# WaterMonitorV2_1.net
KiCad netlist of a schematic drawn in EAGLE
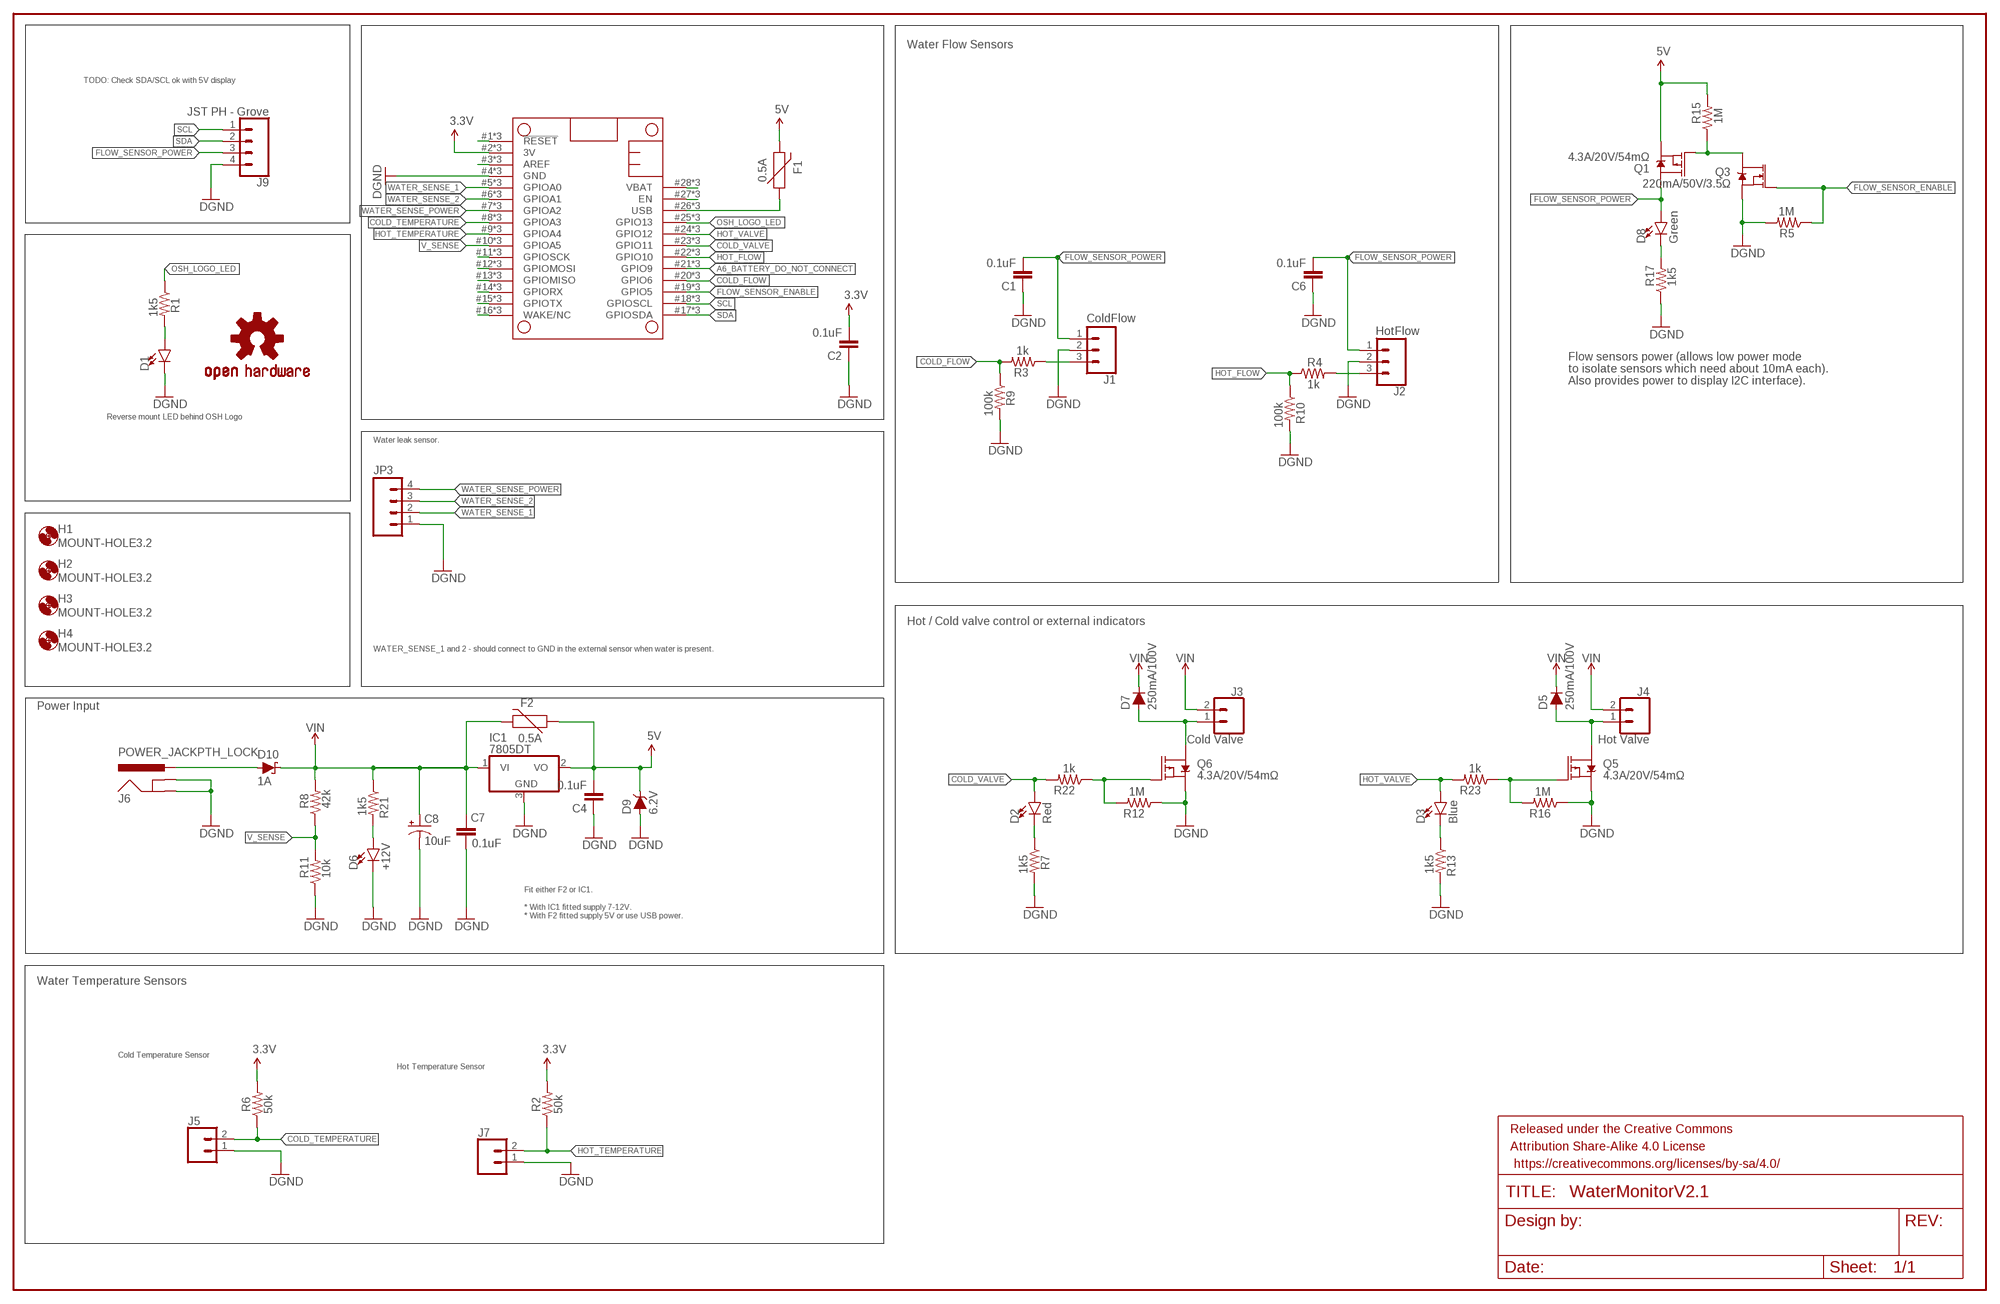
[diagram p0: schematic, sheet 1]

(export (version "E")
  (design (tool "Eeschema 10.0.6"))
  (components
    (comp (ref "C1")
      (value "0.1uF")
      (footprint "eagle-import:0805")
      (libsource (lib "eagle-import") (part "CAP0805"))
    )
    (comp (ref "C2")
      (value "0.1uF")
      (footprint "eagle-import:0805")
      (libsource (lib "eagle-import") (part "CAP0805"))
    )
    (comp (ref "C4")
      (value "0.1uF")
      (footprint "eagle-import:0805")
      (libsource (lib "eagle-import") (part "CAP0805"))
    )
    (comp (ref "C6")
      (value "0.1uF")
      (footprint "eagle-import:0805")
      (libsource (lib "eagle-import") (part "CAP0805"))
    )
    (comp (ref "C7")
      (value "0.1uF")
      (footprint "eagle-import:0805")
      (libsource (lib "eagle-import") (part "CAP0805"))
    )
    (comp (ref "C8")
      (value "10uF")
      (footprint "eagle-import:EIA3216")
      (libsource (lib "eagle-import") (part "10UF-POLAR-EIA3216-16V-10%(TANT)"))
    )
    (comp (ref "D1")
      (value "LED1206-BOTTOM")
      (footprint "eagle-import:LED-1206-BOTTOM")
      (libsource (lib "eagle-import") (part "LED1206-BOTTOM"))
    )
    (comp (ref "D2")
      (value "Red")
      (footprint "eagle-import:LED-1206")
      (libsource (lib "eagle-import") (part "LED-BLUE1206"))
    )
    (comp (ref "D3")
      (value "Blue")
      (footprint "eagle-import:LED-1206")
      (libsource (lib "eagle-import") (part "LED-BLUE1206"))
    )
    (comp (ref "D5")
      (value "250mA/100V")
      (footprint "eagle-import:SOD-323")
      (libsource (lib "eagle-import") (part "DIODE-BAS16J"))
    )
    (comp (ref "D6")
      (value "+12V")
      (footprint "eagle-import:LED-1206")
      (libsource (lib "eagle-import") (part "LED-BLUE1206"))
    )
    (comp (ref "D7")
      (value "250mA/100V")
      (footprint "eagle-import:SOD-323")
      (libsource (lib "eagle-import") (part "DIODE-BAS16J"))
    )
    (comp (ref "D8")
      (value "Green")
      (footprint "eagle-import:LED-1206")
      (libsource (lib "eagle-import") (part "LED-BLUE1206"))
    )
    (comp (ref "D9")
      (value "6.2V")
      (footprint "eagle-import:SOD-323")
      (fields (field (name "MFG") "BZT52C6V2"))
      (libsource (lib "eagle-import") (part "DIODE-ZENER-BZT52C3V6S"))
    )
    (comp (ref "D10")
      (value "1A")
      (footprint "eagle-import:SMA-DIODE")
      (libsource (lib "eagle-import") (part "DIODE-SCHOTTKY-B340A"))
    )
    (comp (ref "F1")
      (value "0.5A")
      (footprint "eagle-import:1206")
      (libsource (lib "eagle-import") (part "PPTC_HALF-AMP"))
    )
    (comp (ref "F2")
      (value "0.5A")
      (footprint "eagle-import:1206")
      (libsource (lib "eagle-import") (part "PPTC_HALF-AMP"))
    )
    (comp (ref "FRAME2")
      (value "FRAME-LEDGER")
      (footprint "eagle-import:CREATIVE_COMMONS")
      (libsource (lib "eagle-import") (part "FRAME-LEDGER"))
    )
    (comp (ref "H1")
      (value "MOUNT-HOLE3.2")
      (footprint "eagle-import:3,2")
      (libsource (lib "eagle-import") (part "MOUNT-HOLE3.2"))
    )
    (comp (ref "H2")
      (value "MOUNT-HOLE3.2")
      (footprint "eagle-import:3,2")
      (libsource (lib "eagle-import") (part "MOUNT-HOLE3.2"))
    )
    (comp (ref "H3")
      (value "MOUNT-HOLE3.2")
      (footprint "eagle-import:3,2")
      (libsource (lib "eagle-import") (part "MOUNT-HOLE3.2"))
    )
    (comp (ref "H4")
      (value "MOUNT-HOLE3.2")
      (footprint "eagle-import:3,2")
      (libsource (lib "eagle-import") (part "MOUNT-HOLE3.2"))
    )
    (comp (ref "IC1")
      (value "7805DT")
      (footprint "eagle-import:TO252")
      (libsource (lib "eagle-import") (part "78DT05"))
    )
    (comp (ref "J1")
      (value "ColdFlow")
      (footprint "eagle-import:JST-HX-3-PTH-VERT")
      (libsource (lib "eagle-import") (part "CONN_03JST-HX-PTH-VERT"))
    )
    (comp (ref "J2")
      (value "HotFlow")
      (footprint "eagle-import:JST-HX-3-PTH-VERT")
      (libsource (lib "eagle-import") (part "CONN_03JST-HX-PTH-VERT"))
    )
    (comp (ref "J3")
      (value "Cold Valve")
      (footprint "eagle-import:SCREWTERMINAL-5MM-2")
      (libsource (lib "eagle-import") (part "CONN_025MM"))
    )
    (comp (ref "J4")
      (value "Hot Valve")
      (footprint "eagle-import:SCREWTERMINAL-5MM-2")
      (libsource (lib "eagle-import") (part "CONN_025MM"))
    )
    (comp (ref "J5")
      (value "CONN_02POLAR")
      (footprint "eagle-import:MOLEX-1X2")
      (libsource (lib "eagle-import") (part "CONN_02POLAR"))
    )
    (comp (ref "J6")
      (value "POWER_JACKPTH_LOCK")
      (footprint "eagle-import:POWER_JACK_PTH_LOCK")
      (libsource (lib "eagle-import") (part "POWER_JACKPTH_LOCK"))
    )
    (comp (ref "J7")
      (value "CONN_02POLAR")
      (footprint "eagle-import:MOLEX-1X2")
      (libsource (lib "eagle-import") (part "CONN_02POLAR"))
    )
    (comp (ref "J9")
      (value "JST PH - Grove")
      (footprint "eagle-import:JST-4-PTH-VERT")
      (libsource (lib "eagle-import") (part "CONN_04JST-PTH-VERT"))
    )
    (comp (ref "JP3")
      (value "M04POLAR")
      (footprint "eagle-import:MOLEX-1X4@1")
      (libsource (lib "eagle-import") (part "M04POLAR"))
    )
    (comp (ref "LOGO1")
      (value "OSHW-LOGOM")
      (footprint "eagle-import:OSHW-LOGO-M")
      (libsource (lib "eagle-import") (part "OSHW-LOGOM"))
    )
    (comp (ref "MS1")
      (value "FEATHERWINGFEATHEWING_BREAKOUT")
      (footprint "eagle-import:FEATHERWING_BREAKOUT")
      (libsource (lib "eagle-import") (part "FEATHERWINGFEATHEWING_BREAKOUT"))
    )
    (comp (ref "Q1")
      (value "4.3A/20V/54mΩ")
      (footprint "eagle-import:SOT23-3")
      (libsource (lib "eagle-import") (part "MOSFET_PCH-IRLML2244"))
    )
    (comp (ref "Q3")
      (value "220mA/50V/3.5Ω")
      (footprint "eagle-import:SOT23-3")
      (libsource (lib "eagle-import") (part "MOSFET-NCH-BSS138"))
    )
    (comp (ref "Q5")
      (value "4.3A/20V/54mΩ")
      (footprint "eagle-import:SOT23-3")
      (libsource (lib "eagle-import") (part "MOSFET_PCH-IRLML2244"))
    )
    (comp (ref "Q6")
      (value "4.3A/20V/54mΩ")
      (footprint "eagle-import:SOT23-3")
      (libsource (lib "eagle-import") (part "MOSFET_PCH-IRLML2244"))
    )
    (comp (ref "R1")
      (value "1k5")
      (footprint "eagle-import:0805")
      (libsource (lib "eagle-import") (part "RESISTOR0805"))
    )
    (comp (ref "R2")
      (value "50k")
      (footprint "eagle-import:0805")
      (libsource (lib "eagle-import") (part "RESISTOR0805"))
    )
    (comp (ref "R3")
      (value "1k")
      (footprint "eagle-import:0805")
      (libsource (lib "eagle-import") (part "RESISTOR0805"))
    )
    (comp (ref "R4")
      (value "1k")
      (footprint "eagle-import:0805")
      (libsource (lib "eagle-import") (part "RESISTOR0805"))
    )
    (comp (ref "R5")
      (value "1M")
      (footprint "eagle-import:0805")
      (libsource (lib "eagle-import") (part "RESISTOR0805"))
    )
    (comp (ref "R6")
      (value "50k")
      (footprint "eagle-import:0805")
      (libsource (lib "eagle-import") (part "RESISTOR0805"))
    )
    (comp (ref "R7")
      (value "1k5")
      (footprint "eagle-import:0805")
      (libsource (lib "eagle-import") (part "RESISTOR0805"))
    )
    (comp (ref "R8")
      (value "42k")
      (footprint "eagle-import:0805")
      (libsource (lib "eagle-import") (part "RESISTOR0805"))
    )
    (comp (ref "R9")
      (value "100k")
      (footprint "eagle-import:0805")
      (libsource (lib "eagle-import") (part "RESISTOR0805"))
    )
    (comp (ref "R10")
      (value "100k")
      (footprint "eagle-import:0805")
      (libsource (lib "eagle-import") (part "RESISTOR0805"))
    )
    (comp (ref "R11")
      (value "10k")
      (footprint "eagle-import:0805")
      (libsource (lib "eagle-import") (part "RESISTOR0805"))
    )
    (comp (ref "R12")
      (value "1M")
      (footprint "eagle-import:0805")
      (libsource (lib "eagle-import") (part "RESISTOR0805"))
    )
    (comp (ref "R13")
      (value "1k5")
      (footprint "eagle-import:0805")
      (libsource (lib "eagle-import") (part "RESISTOR0805"))
    )
    (comp (ref "R15")
      (value "1M")
      (footprint "eagle-import:0805")
      (libsource (lib "eagle-import") (part "RESISTOR0805"))
    )
    (comp (ref "R16")
      (value "1M")
      (footprint "eagle-import:0805")
      (libsource (lib "eagle-import") (part "RESISTOR0805"))
    )
    (comp (ref "R17")
      (value "1k5")
      (footprint "eagle-import:0805")
      (libsource (lib "eagle-import") (part "RESISTOR0805"))
    )
    (comp (ref "R21")
      (value "1k5")
      (footprint "eagle-import:0805")
      (libsource (lib "eagle-import") (part "RESISTOR0805"))
    )
    (comp (ref "R22")
      (value "1k")
      (footprint "eagle-import:0805")
      (libsource (lib "eagle-import") (part "RESISTOR0805"))
    )
    (comp (ref "R23")
      (value "1k")
      (footprint "eagle-import:0805")
      (libsource (lib "eagle-import") (part "RESISTOR0805"))
    )
  )
  (nets
    (net (code "1") (name "3.3V") (class "Default")
      (node (ref "C2") (pin "2") (pinfunction "2_2") (pintype "passive"))
      (node (ref "MS1") (pin "#2") (pinfunction "3V_#2") (pintype "power_in"))
      (node (ref "MS1") (pin "2") (pinfunction "3V_2") (pintype "power_in"))
      (node (ref "MS1") (pin "@2") (pinfunction "3V_@2") (pintype "power_in"))
      (node (ref "R2") (pin "2") (pinfunction "2_2") (pintype "passive"))
      (node (ref "R6") (pin "2") (pinfunction "2_2") (pintype "passive"))
    )
    (net (code "2") (name "5V") (class "Default")
      (node (ref "C4") (pin "2") (pinfunction "2_2") (pintype "passive"))
      (node (ref "D9") (pin "C") (pinfunction "C_C") (pintype "passive"))
      (node (ref "F1") (pin "2") (pinfunction "2_2") (pintype "bidirectional"))
      (node (ref "F2") (pin "1") (pinfunction "1_1") (pintype "bidirectional"))
      (node (ref "IC1") (pin "2") (pinfunction "VO_2") (pintype "passive"))
      (node (ref "Q1") (pin "2") (pinfunction "S_2") (pintype "bidirectional"))
      (node (ref "R15") (pin "2") (pinfunction "2_2") (pintype "passive"))
    )
    (net (code "3") (name "A6_BATTERY_DO_NOT_CONNECT") (class "Default")
      (node (ref "MS1") (pin "#21") (pinfunction "GPIO9_#21") (pintype "bidirectional"))
      (node (ref "MS1") (pin "21") (pinfunction "GPIO9_21") (pintype "bidirectional"))
      (node (ref "MS1") (pin "@21") (pinfunction "GPIO9_@21") (pintype "bidirectional"))
    )
    (net (code "4") (name "COLD_FLOW") (class "Default")
      (node (ref "MS1") (pin "#20") (pinfunction "GPIO6_#20") (pintype "bidirectional"))
      (node (ref "MS1") (pin "20") (pinfunction "GPIO6_20") (pintype "bidirectional"))
      (node (ref "MS1") (pin "@20") (pinfunction "GPIO6_@20") (pintype "bidirectional"))
      (node (ref "R3") (pin "2") (pinfunction "2_2") (pintype "passive"))
      (node (ref "R9") (pin "1") (pinfunction "1_1") (pintype "passive"))
    )
    (net (code "5") (name "COLD_TEMPERATURE") (class "Default")
      (node (ref "J5") (pin "2") (pinfunction "2_2") (pintype "passive"))
      (node (ref "MS1") (pin "#8") (pinfunction "GPIOA3_#8") (pintype "bidirectional"))
      (node (ref "MS1") (pin "8") (pinfunction "GPIOA3_8") (pintype "bidirectional"))
      (node (ref "MS1") (pin "@8") (pinfunction "GPIOA3_@8") (pintype "bidirectional"))
      (node (ref "R6") (pin "1") (pinfunction "1_1") (pintype "passive"))
    )
    (net (code "6") (name "COLD_VALVE") (class "Default")
      (node (ref "D2") (pin "A") (pinfunction "A_A") (pintype "passive"))
      (node (ref "MS1") (pin "#23") (pinfunction "GPIO11_#23") (pintype "bidirectional"))
      (node (ref "MS1") (pin "23") (pinfunction "GPIO11_23") (pintype "bidirectional"))
      (node (ref "MS1") (pin "@23") (pinfunction "GPIO11_@23") (pintype "bidirectional"))
      (node (ref "R22") (pin "2") (pinfunction "2_2") (pintype "passive"))
    )
    (net (code "7") (name "DGND") (class "Default")
      (node (ref "C1") (pin "1") (pinfunction "1_1") (pintype "passive"))
      (node (ref "C2") (pin "1") (pinfunction "1_1") (pintype "passive"))
      (node (ref "C4") (pin "1") (pinfunction "1_1") (pintype "passive"))
      (node (ref "C6") (pin "1") (pinfunction "1_1") (pintype "passive"))
      (node (ref "C7") (pin "1") (pinfunction "1_1") (pintype "passive"))
      (node (ref "C8") (pin "-") (pinfunction "-_-") (pintype "passive"))
      (node (ref "D1") (pin "C") (pinfunction "C_C") (pintype "passive"))
      (node (ref "D6") (pin "C") (pinfunction "C_C") (pintype "passive"))
      (node (ref "D9") (pin "A") (pinfunction "A_A") (pintype "passive"))
      (node (ref "IC1") (pin "3") (pinfunction "GND_3") (pintype "passive"))
      (node (ref "J1") (pin "2") (pinfunction "2_2") (pintype "passive"))
      (node (ref "J2") (pin "2") (pinfunction "2_2") (pintype "passive"))
      (node (ref "J5") (pin "1") (pinfunction "1_1") (pintype "passive"))
      (node (ref "J6") (pin "GND") (pinfunction "GND_GND") (pintype "bidirectional"))
      (node (ref "J6") (pin "GNDBREAK") (pinfunction "GNDBREAK_GNDBREAK") (pintype "bidirectional"))
      (node (ref "J7") (pin "1") (pinfunction "1_1") (pintype "passive"))
      (node (ref "J9") (pin "4") (pinfunction "4_4") (pintype "passive"))
      (node (ref "JP3") (pin "1") (pinfunction "1_1") (pintype "passive"))
      (node (ref "MS1") (pin "#4") (pinfunction "GND_#4") (pintype "power_in"))
      (node (ref "MS1") (pin "4") (pinfunction "GND_4") (pintype "power_in"))
      (node (ref "MS1") (pin "@4") (pinfunction "GND_@4") (pintype "power_in"))
      (node (ref "Q3") (pin "2") (pinfunction "S_2") (pintype "bidirectional"))
      (node (ref "Q5") (pin "2") (pinfunction "S_2") (pintype "bidirectional"))
      (node (ref "Q6") (pin "2") (pinfunction "S_2") (pintype "bidirectional"))
      (node (ref "R10") (pin "2") (pinfunction "2_2") (pintype "passive"))
      (node (ref "R11") (pin "1") (pinfunction "1_1") (pintype "passive"))
      (node (ref "R12") (pin "1") (pinfunction "1_1") (pintype "passive"))
      (node (ref "R13") (pin "2") (pinfunction "2_2") (pintype "passive"))
      (node (ref "R16") (pin "1") (pinfunction "1_1") (pintype "passive"))
      (node (ref "R17") (pin "1") (pinfunction "1_1") (pintype "passive"))
      (node (ref "R5") (pin "2") (pinfunction "2_2") (pintype "passive"))
      (node (ref "R7") (pin "2") (pinfunction "2_2") (pintype "passive"))
      (node (ref "R9") (pin "2") (pinfunction "2_2") (pintype "passive"))
    )
    (net (code "8") (name "FLOW_SENSOR_ENABLE") (class "Default")
      (node (ref "MS1") (pin "#19") (pinfunction "GPIO5_#19") (pintype "bidirectional"))
      (node (ref "MS1") (pin "19") (pinfunction "GPIO5_19") (pintype "bidirectional"))
      (node (ref "MS1") (pin "@19") (pinfunction "GPIO5_@19") (pintype "bidirectional"))
      (node (ref "Q3") (pin "1") (pinfunction "G_1") (pintype "bidirectional"))
      (node (ref "R5") (pin "1") (pinfunction "1_1") (pintype "passive"))
    )
    (net (code "9") (name "FLOW_SENSOR_POWER") (class "Default")
      (node (ref "C1") (pin "2") (pinfunction "2_2") (pintype "passive"))
      (node (ref "C6") (pin "2") (pinfunction "2_2") (pintype "passive"))
      (node (ref "D8") (pin "A") (pinfunction "A_A") (pintype "passive"))
      (node (ref "J1") (pin "1") (pinfunction "1_1") (pintype "passive"))
      (node (ref "J2") (pin "1") (pinfunction "1_1") (pintype "passive"))
      (node (ref "J9") (pin "3") (pinfunction "3_3") (pintype "passive"))
      (node (ref "Q1") (pin "3") (pinfunction "D_3") (pintype "bidirectional"))
    )
    (net (code "10") (name "HOT_FLOW") (class "Default")
      (node (ref "MS1") (pin "#22") (pinfunction "GPIO10_#22") (pintype "bidirectional"))
      (node (ref "MS1") (pin "22") (pinfunction "GPIO10_22") (pintype "bidirectional"))
      (node (ref "MS1") (pin "@22") (pinfunction "GPIO10_@22") (pintype "bidirectional"))
      (node (ref "R10") (pin "1") (pinfunction "1_1") (pintype "passive"))
      (node (ref "R4") (pin "1") (pinfunction "1_1") (pintype "passive"))
    )
    (net (code "11") (name "HOT_TEMPERATURE") (class "Default")
      (node (ref "J7") (pin "2") (pinfunction "2_2") (pintype "passive"))
      (node (ref "MS1") (pin "#9") (pinfunction "GPIOA4_#9") (pintype "bidirectional"))
      (node (ref "MS1") (pin "9") (pinfunction "GPIOA4_9") (pintype "bidirectional"))
      (node (ref "MS1") (pin "@9") (pinfunction "GPIOA4_@9") (pintype "bidirectional"))
      (node (ref "R2") (pin "1") (pinfunction "1_1") (pintype "passive"))
    )
    (net (code "12") (name "HOT_VALVE") (class "Default")
      (node (ref "D3") (pin "A") (pinfunction "A_A") (pintype "passive"))
      (node (ref "MS1") (pin "#24") (pinfunction "GPIO12_#24") (pintype "bidirectional"))
      (node (ref "MS1") (pin "24") (pinfunction "GPIO12_24") (pintype "bidirectional"))
      (node (ref "MS1") (pin "@24") (pinfunction "GPIO12_@24") (pintype "bidirectional"))
      (node (ref "R23") (pin "2") (pinfunction "2_2") (pintype "passive"))
    )
    (net (code "13") (name "Net-(D1-PadA)") (class "Default")
      (node (ref "D1") (pin "A") (pinfunction "A_A") (pintype "passive"))
      (node (ref "R1") (pin "2") (pinfunction "2_2") (pintype "passive"))
    )
    (net (code "14") (name "Net-(D2-PadC)") (class "Default")
      (node (ref "D2") (pin "C") (pinfunction "C_C") (pintype "passive"))
      (node (ref "R7") (pin "1") (pinfunction "1_1") (pintype "passive"))
    )
    (net (code "15") (name "Net-(D3-PadC)") (class "Default")
      (node (ref "D3") (pin "C") (pinfunction "C_C") (pintype "passive"))
      (node (ref "R13") (pin "1") (pinfunction "1_1") (pintype "passive"))
    )
    (net (code "16") (name "Net-(D6-PadA)") (class "Default")
      (node (ref "D6") (pin "A") (pinfunction "A_A") (pintype "passive"))
      (node (ref "R21") (pin "2") (pinfunction "2_2") (pintype "passive"))
    )
    (net (code "17") (name "Net-(D8-PadC)") (class "Default")
      (node (ref "D8") (pin "C") (pinfunction "C_C") (pintype "passive"))
      (node (ref "R17") (pin "2") (pinfunction "2_2") (pintype "passive"))
    )
    (net (code "18") (name "Net-(D10-PadA)") (class "Default")
      (node (ref "D10") (pin "A") (pinfunction "A_A") (pintype "passive"))
      (node (ref "J6") (pin "PWR") (pinfunction "PWR_PWR") (pintype "bidirectional"))
    )
    (net (code "19") (name "Net-(F1-Pad1)") (class "Default")
      (node (ref "F1") (pin "1") (pinfunction "1_1") (pintype "bidirectional"))
      (node (ref "MS1") (pin "#26") (pinfunction "USB_#26") (pintype "power_in"))
      (node (ref "MS1") (pin "26") (pinfunction "USB_26") (pintype "power_in"))
      (node (ref "MS1") (pin "@26") (pinfunction "USB_@26") (pintype "power_in"))
    )
    (net (code "20") (name "Net-(J1-Pad3)") (class "Default")
      (node (ref "J1") (pin "3") (pinfunction "3_3") (pintype "passive"))
      (node (ref "R3") (pin "1") (pinfunction "1_1") (pintype "passive"))
    )
    (net (code "21") (name "Net-(J2-Pad3)") (class "Default")
      (node (ref "J2") (pin "3") (pinfunction "3_3") (pintype "passive"))
      (node (ref "R4") (pin "2") (pinfunction "2_2") (pintype "passive"))
    )
    (net (code "22") (name "Net-(MS1-AREF-Pad#3)") (class "Default")
      (node (ref "MS1") (pin "#3") (pinfunction "AREF_#3") (pintype "passive"))
      (node (ref "MS1") (pin "3") (pinfunction "AREF_3") (pintype "passive"))
      (node (ref "MS1") (pin "@3") (pinfunction "AREF_@3") (pintype "passive"))
    )
    (net (code "23") (name "Net-(MS1-EN-Pad#27)") (class "Default")
      (node (ref "MS1") (pin "#27") (pinfunction "EN_#27") (pintype "passive"))
      (node (ref "MS1") (pin "27") (pinfunction "EN_27") (pintype "passive"))
      (node (ref "MS1") (pin "@27") (pinfunction "EN_@27") (pintype "passive"))
    )
    (net (code "24") (name "Net-(MS1-GPIOMISO-Pad#13)") (class "Default")
      (node (ref "MS1") (pin "#13") (pinfunction "GPIOMISO_#13") (pintype "bidirectional"))
      (node (ref "MS1") (pin "13") (pinfunction "GPIOMISO_13") (pintype "bidirectional"))
      (node (ref "MS1") (pin "@13") (pinfunction "GPIOMISO_@13") (pintype "bidirectional"))
    )
    (net (code "25") (name "Net-(MS1-GPIOMOSI-Pad#12)") (class "Default")
      (node (ref "MS1") (pin "#12") (pinfunction "GPIOMOSI_#12") (pintype "bidirectional"))
      (node (ref "MS1") (pin "12") (pinfunction "GPIOMOSI_12") (pintype "bidirectional"))
      (node (ref "MS1") (pin "@12") (pinfunction "GPIOMOSI_@12") (pintype "bidirectional"))
    )
    (net (code "26") (name "Net-(MS1-GPIORX-Pad#14)") (class "Default")
      (node (ref "MS1") (pin "#14") (pinfunction "GPIORX_#14") (pintype "bidirectional"))
      (node (ref "MS1") (pin "14") (pinfunction "GPIORX_14") (pintype "bidirectional"))
      (node (ref "MS1") (pin "@14") (pinfunction "GPIORX_@14") (pintype "bidirectional"))
    )
    (net (code "27") (name "Net-(MS1-GPIOSCK-Pad#11)") (class "Default")
      (node (ref "MS1") (pin "#11") (pinfunction "GPIOSCK_#11") (pintype "bidirectional"))
      (node (ref "MS1") (pin "11") (pinfunction "GPIOSCK_11") (pintype "bidirectional"))
      (node (ref "MS1") (pin "@11") (pinfunction "GPIOSCK_@11") (pintype "bidirectional"))
    )
    (net (code "28") (name "Net-(MS1-GPIOTX-Pad#15)") (class "Default")
      (node (ref "MS1") (pin "#15") (pinfunction "GPIOTX_#15") (pintype "bidirectional"))
      (node (ref "MS1") (pin "15") (pinfunction "GPIOTX_15") (pintype "bidirectional"))
      (node (ref "MS1") (pin "@15") (pinfunction "GPIOTX_@15") (pintype "bidirectional"))
    )
    (net (code "29") (name "Net-(MS1-VBAT-Pad#28)") (class "Default")
      (node (ref "MS1") (pin "#28") (pinfunction "VBAT_#28") (pintype "power_in"))
      (node (ref "MS1") (pin "28") (pinfunction "VBAT_28") (pintype "power_in"))
      (node (ref "MS1") (pin "@28") (pinfunction "VBAT_@28") (pintype "power_in"))
    )
    (net (code "30") (name "Net-(MS1-WAKE{slash}NC-Pad#16)") (class "Default")
      (node (ref "MS1") (pin "#16") (pinfunction "WAKE/NC_#16") (pintype "passive"))
      (node (ref "MS1") (pin "16") (pinfunction "WAKE/NC_16") (pintype "passive"))
      (node (ref "MS1") (pin "@16") (pinfunction "WAKE/NC_@16") (pintype "passive"))
    )
    (net (code "31") (name "Net-(MS1-~{RESET}-Pad#1)") (class "Default")
      (node (ref "MS1") (pin "#1") (pinfunction "~{RESET}_#1") (pintype "input"))
      (node (ref "MS1") (pin "1") (pinfunction "~{RESET}_1") (pintype "input"))
      (node (ref "MS1") (pin "@1") (pinfunction "~{RESET}_@1") (pintype "input"))
    )
    (net (code "32") (name "Net-(Q1-G)") (class "Default")
      (node (ref "Q1") (pin "1") (pinfunction "G_1") (pintype "bidirectional"))
      (node (ref "Q3") (pin "3") (pinfunction "D_3") (pintype "bidirectional"))
      (node (ref "R15") (pin "1") (pinfunction "1_1") (pintype "passive"))
    )
    (net (code "33") (name "Net-(Q5-D)") (class "Default")
      (node (ref "D5") (pin "A") (pinfunction "A_A") (pintype "passive"))
      (node (ref "J4") (pin "1") (pinfunction "1_1") (pintype "passive"))
      (node (ref "Q5") (pin "3") (pinfunction "D_3") (pintype "bidirectional"))
    )
    (net (code "34") (name "Net-(Q5-G)") (class "Default")
      (node (ref "Q5") (pin "1") (pinfunction "G_1") (pintype "bidirectional"))
      (node (ref "R16") (pin "2") (pinfunction "2_2") (pintype "passive"))
      (node (ref "R23") (pin "1") (pinfunction "1_1") (pintype "passive"))
    )
    (net (code "35") (name "Net-(Q6-D)") (class "Default")
      (node (ref "D7") (pin "A") (pinfunction "A_A") (pintype "passive"))
      (node (ref "J3") (pin "1") (pinfunction "1_1") (pintype "passive"))
      (node (ref "Q6") (pin "3") (pinfunction "D_3") (pintype "bidirectional"))
    )
    (net (code "36") (name "Net-(Q6-G)") (class "Default")
      (node (ref "Q6") (pin "1") (pinfunction "G_1") (pintype "bidirectional"))
      (node (ref "R12") (pin "2") (pinfunction "2_2") (pintype "passive"))
      (node (ref "R22") (pin "1") (pinfunction "1_1") (pintype "passive"))
    )
    (net (code "37") (name "OSH_LOGO_LED") (class "Default")
      (node (ref "MS1") (pin "#25") (pinfunction "GPIO13_#25") (pintype "bidirectional"))
      (node (ref "MS1") (pin "25") (pinfunction "GPIO13_25") (pintype "bidirectional"))
      (node (ref "MS1") (pin "@25") (pinfunction "GPIO13_@25") (pintype "bidirectional"))
      (node (ref "R1") (pin "1") (pinfunction "1_1") (pintype "passive"))
    )
    (net (code "38") (name "SCL") (class "Default")
      (node (ref "J9") (pin "1") (pinfunction "1_1") (pintype "passive"))
      (node (ref "MS1") (pin "#18") (pinfunction "GPIOSCL_#18") (pintype "bidirectional"))
      (node (ref "MS1") (pin "18") (pinfunction "GPIOSCL_18") (pintype "bidirectional"))
      (node (ref "MS1") (pin "@!8") (pinfunction "GPIOSCL_@!8") (pintype "bidirectional"))
    )
    (net (code "39") (name "SDA") (class "Default")
      (node (ref "J9") (pin "2") (pinfunction "2_2") (pintype "passive"))
      (node (ref "MS1") (pin "#17") (pinfunction "GPIOSDA_#17") (pintype "bidirectional"))
      (node (ref "MS1") (pin "17") (pinfunction "GPIOSDA_17") (pintype "bidirectional"))
      (node (ref "MS1") (pin "@17") (pinfunction "GPIOSDA_@17") (pintype "bidirectional"))
    )
    (net (code "40") (name "VIN") (class "Default")
      (node (ref "C7") (pin "2") (pinfunction "2_2") (pintype "passive"))
      (node (ref "C8") (pin "+") (pinfunction "+_+") (pintype "passive"))
      (node (ref "D10") (pin "C") (pinfunction "C_C") (pintype "passive"))
      (node (ref "D5") (pin "C") (pinfunction "C_C") (pintype "passive"))
      (node (ref "D7") (pin "C") (pinfunction "C_C") (pintype "passive"))
      (node (ref "F2") (pin "2") (pinfunction "2_2") (pintype "bidirectional"))
      (node (ref "IC1") (pin "1") (pinfunction "VI_1") (pintype "input"))
      (node (ref "J3") (pin "2") (pinfunction "2_2") (pintype "passive"))
      (node (ref "J4") (pin "2") (pinfunction "2_2") (pintype "passive"))
      (node (ref "R21") (pin "1") (pinfunction "1_1") (pintype "passive"))
      (node (ref "R8") (pin "2") (pinfunction "2_2") (pintype "passive"))
    )
    (net (code "41") (name "V_SENSE") (class "Default")
      (node (ref "MS1") (pin "#10") (pinfunction "GPIOA5_#10") (pintype "bidirectional"))
      (node (ref "MS1") (pin "10") (pinfunction "GPIOA5_10") (pintype "bidirectional"))
      (node (ref "MS1") (pin "@10") (pinfunction "GPIOA5_@10") (pintype "bidirectional"))
      (node (ref "R11") (pin "2") (pinfunction "2_2") (pintype "passive"))
      (node (ref "R8") (pin "1") (pinfunction "1_1") (pintype "passive"))
    )
    (net (code "42") (name "WATER_SENSE_1") (class "Default")
      (node (ref "JP3") (pin "2") (pinfunction "2_2") (pintype "passive"))
      (node (ref "MS1") (pin "#5") (pinfunction "GPIOA0_#5") (pintype "bidirectional"))
      (node (ref "MS1") (pin "5") (pinfunction "GPIOA0_5") (pintype "bidirectional"))
      (node (ref "MS1") (pin "@5") (pinfunction "GPIOA0_@5") (pintype "bidirectional"))
    )
    (net (code "43") (name "WATER_SENSE_2") (class "Default")
      (node (ref "JP3") (pin "3") (pinfunction "3_3") (pintype "passive"))
      (node (ref "MS1") (pin "#6") (pinfunction "GPIOA1_#6") (pintype "bidirectional"))
      (node (ref "MS1") (pin "6") (pinfunction "GPIOA1_6") (pintype "bidirectional"))
      (node (ref "MS1") (pin "@6") (pinfunction "GPIOA1_@6") (pintype "bidirectional"))
    )
    (net (code "44") (name "WATER_SENSE_POWER") (class "Default")
      (node (ref "JP3") (pin "4") (pinfunction "4_4") (pintype "passive"))
      (node (ref "MS1") (pin "#7") (pinfunction "GPIOA2_#7") (pintype "bidirectional"))
      (node (ref "MS1") (pin "7") (pinfunction "GPIOA2_7") (pintype "bidirectional"))
      (node (ref "MS1") (pin "@7") (pinfunction "GPIOA2_@7") (pintype "bidirectional"))
    )
  )
)
